# DIAGNOSTIC_ADC.net
KiCad netlist of a schematic drawn in Altium Designer
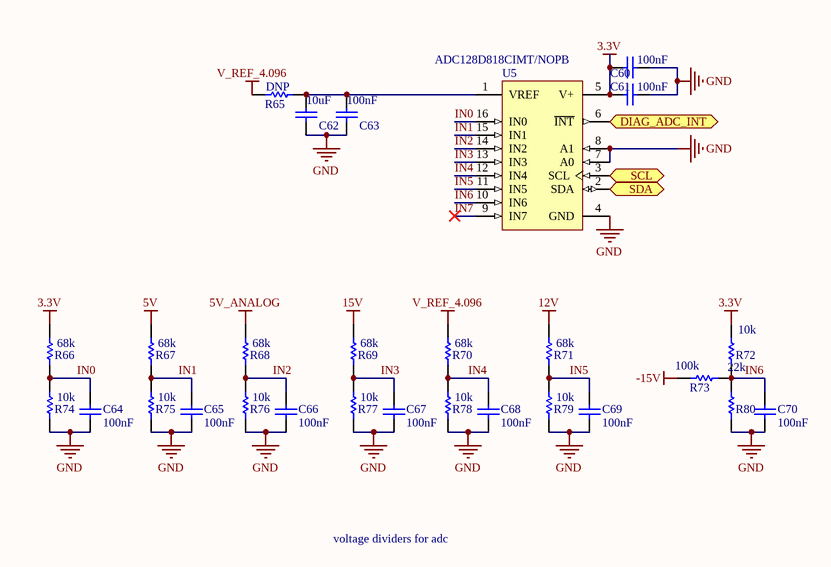
[diagram p0: DIAGNOSTIC_ADC.SchDoc]

(export (version "E")
  (design (tool "Eeschema 10.0.6"))
  (components
    (comp (ref "C60")
      (value "100nF")
      (footprint "CAPC0402(1005)60_L")
      (description "0402 (1005 Metric) Chip Capacitor")
      (fields (field (name "Comment") "CAP0402"))
      (libsource (lib "Altium Content Vault") (part "CMP-1590-00004-1"))
    )
    (comp (ref "C61")
      (value "100nF")
      (footprint "CAPC0402(1005)60_L")
      (description "0402 (1005 Metric) Chip Capacitor")
      (fields (field (name "Comment") "CAP0402"))
      (libsource (lib "Altium Content Vault") (part "CMP-1590-00004-1"))
    )
    (comp (ref "C62")
      (value "10uF")
      (footprint "CAPC0805(2012)145_L")
      (description "0805 (2012 Metric) Chip Capacitor")
      (fields (field (name "Comment") "CAP0805"))
      (libsource (lib "Altium Content Vault") (part "CMP-1590-00003-1"))
    )
    (comp (ref "C63")
      (value "100nF")
      (footprint "CAPC0402(1005)60_L")
      (description "0402 (1005 Metric) Chip Capacitor")
      (fields (field (name "Comment") "CAP0402"))
      (libsource (lib "Altium Content Vault") (part "CMP-1590-00004-1"))
    )
    (comp (ref "C64")
      (value "100nF")
      (footprint "CAPC0402(1005)60_L")
      (description "0402 (1005 Metric) Chip Capacitor")
      (fields (field (name "Comment") "CAP0402"))
      (libsource (lib "Altium Content Vault") (part "CMP-1590-00004-1"))
    )
    (comp (ref "C65")
      (value "100nF")
      (footprint "CAPC0402(1005)60_L")
      (description "0402 (1005 Metric) Chip Capacitor")
      (fields (field (name "Comment") "CAP0402"))
      (libsource (lib "Altium Content Vault") (part "CMP-1590-00004-1"))
    )
    (comp (ref "C66")
      (value "100nF")
      (footprint "CAPC0402(1005)60_L")
      (description "0402 (1005 Metric) Chip Capacitor")
      (fields (field (name "Comment") "CAP0402"))
      (libsource (lib "Altium Content Vault") (part "CMP-1590-00004-1"))
    )
    (comp (ref "C67")
      (value "100nF")
      (footprint "CAPC0402(1005)60_L")
      (description "0402 (1005 Metric) Chip Capacitor")
      (fields (field (name "Comment") "CAP0402"))
      (libsource (lib "Altium Content Vault") (part "CMP-1590-00004-1"))
    )
    (comp (ref "C68")
      (value "100nF")
      (footprint "CAPC0402(1005)60_L")
      (description "0402 (1005 Metric) Chip Capacitor")
      (fields (field (name "Comment") "CAP0402"))
      (libsource (lib "Altium Content Vault") (part "CMP-1590-00004-1"))
    )
    (comp (ref "C69")
      (value "100nF")
      (footprint "CAPC0402(1005)60_L")
      (description "0402 (1005 Metric) Chip Capacitor")
      (fields (field (name "Comment") "CAP0402"))
      (libsource (lib "Altium Content Vault") (part "CMP-1590-00004-1"))
    )
    (comp (ref "C70")
      (value "100nF")
      (footprint "CAPC0402(1005)60_L")
      (description "0402 (1005 Metric) Chip Capacitor")
      (fields (field (name "Comment") "CAP0402"))
      (libsource (lib "Altium Content Vault") (part "CMP-1590-00004-1"))
    )
    (comp (ref "R65")
      (value "DNP")
      (footprint "RESC0402(1005)_L")
      (description "0402 (1005 Metric) Chip Resistor")
      (fields (field (name "Comment") "RES0402"))
      (libsource (lib "Altium Content Vault") (part "CMP-1591-00004-1"))
    )
    (comp (ref "R66")
      (value "68k")
      (footprint "RESC0402(1005)_L")
      (description "0402 (1005 Metric) Chip Resistor")
      (fields (field (name "Comment") "RES0402"))
      (libsource (lib "Altium Content Vault") (part "CMP-1591-00004-1"))
    )
    (comp (ref "R67")
      (value "68k")
      (footprint "RESC0402(1005)_L")
      (description "0402 (1005 Metric) Chip Resistor")
      (fields (field (name "Comment") "RES0402"))
      (libsource (lib "Altium Content Vault") (part "CMP-1591-00004-1"))
    )
    (comp (ref "R68")
      (value "68k")
      (footprint "RESC0402(1005)_L")
      (description "0402 (1005 Metric) Chip Resistor")
      (fields (field (name "Comment") "RES0402"))
      (libsource (lib "Altium Content Vault") (part "CMP-1591-00004-1"))
    )
    (comp (ref "R69")
      (value "68k")
      (footprint "RESC0402(1005)_L")
      (description "0402 (1005 Metric) Chip Resistor")
      (fields (field (name "Comment") "RES0402"))
      (libsource (lib "Altium Content Vault") (part "CMP-1591-00004-1"))
    )
    (comp (ref "R70")
      (value "68k")
      (footprint "RESC0402(1005)_L")
      (description "0402 (1005 Metric) Chip Resistor")
      (fields (field (name "Comment") "RES0402"))
      (libsource (lib "Altium Content Vault") (part "CMP-1591-00004-1"))
    )
    (comp (ref "R71")
      (value "68k")
      (footprint "RESC0402(1005)_L")
      (description "0402 (1005 Metric) Chip Resistor")
      (fields (field (name "Comment") "RES0402"))
      (libsource (lib "Altium Content Vault") (part "CMP-1591-00004-1"))
    )
    (comp (ref "R72")
      (value "10k")
      (footprint "RESC0402(1005)_L")
      (description "0402 (1005 Metric) Chip Resistor")
      (fields (field (name "Comment") "RES0402"))
      (libsource (lib "Altium Content Vault") (part "CMP-1591-00004-1"))
    )
    (comp (ref "R73")
      (value "100k")
      (footprint "RESC0402(1005)_L")
      (description "0402 (1005 Metric) Chip Resistor")
      (fields (field (name "Comment") "RES0402"))
      (libsource (lib "Altium Content Vault") (part "CMP-1591-00004-1"))
    )
    (comp (ref "R74")
      (value "10k")
      (footprint "RESC0402(1005)_L")
      (description "0402 (1005 Metric) Chip Resistor")
      (fields (field (name "Comment") "RES0402"))
      (libsource (lib "Altium Content Vault") (part "CMP-1591-00004-1"))
    )
    (comp (ref "R75")
      (value "10k")
      (footprint "RESC0402(1005)_L")
      (description "0402 (1005 Metric) Chip Resistor")
      (fields (field (name "Comment") "RES0402"))
      (libsource (lib "Altium Content Vault") (part "CMP-1591-00004-1"))
    )
    (comp (ref "R76")
      (value "10k")
      (footprint "RESC0402(1005)_L")
      (description "0402 (1005 Metric) Chip Resistor")
      (fields (field (name "Comment") "RES0402"))
      (libsource (lib "Altium Content Vault") (part "CMP-1591-00004-1"))
    )
    (comp (ref "R77")
      (value "10k")
      (footprint "RESC0402(1005)_L")
      (description "0402 (1005 Metric) Chip Resistor")
      (fields (field (name "Comment") "RES0402"))
      (libsource (lib "Altium Content Vault") (part "CMP-1591-00004-1"))
    )
    (comp (ref "R78")
      (value "10k")
      (footprint "RESC0402(1005)_L")
      (description "0402 (1005 Metric) Chip Resistor")
      (fields (field (name "Comment") "RES0402"))
      (libsource (lib "Altium Content Vault") (part "CMP-1591-00004-1"))
    )
    (comp (ref "R79")
      (value "10k")
      (footprint "RESC0402(1005)_L")
      (description "0402 (1005 Metric) Chip Resistor")
      (fields (field (name "Comment") "RES0402"))
      (libsource (lib "Altium Content Vault") (part "CMP-1591-00004-1"))
    )
    (comp (ref "R80")
      (value "22k")
      (footprint "RESC0402(1005)_L")
      (description "0402 (1005 Metric) Chip Resistor")
      (fields (field (name "Comment") "RES0402"))
      (libsource (lib "Altium Content Vault") (part "CMP-1591-00004-1"))
    )
    (comp (ref "U5")
      (value "ADC128D818CIMT/NOPB")
      (footprint "MTC16_N")
      (fields (field (name "MANUFACTURER") "National Semiconductor"))
      (libsource (lib "Altium Content Vault") (part "CON-ADC-ADC128D818-16"))
    )
  )
  (nets
    (net (code "1") (name "-15V") (class "Default")
      (node (ref "R73") (pin "1") (pinfunction "1_1") (pintype "passive"))
    )
    (net (code "2") (name "/DIAG_ADC_INT") (class "Default")
      (node (ref "U5") (pin "6") (pinfunction "~{INT}_6") (pintype "output"))
    )
    (net (code "3") (name "/IN0") (class "Default")
      (node (ref "C64") (pin "2") (pinfunction "2_2") (pintype "passive"))
      (node (ref "R66") (pin "2") (pinfunction "2_2") (pintype "passive"))
      (node (ref "R74") (pin "1") (pinfunction "1_1") (pintype "passive"))
      (node (ref "U5") (pin "16") (pinfunction "IN0_16") (pintype "input"))
    )
    (net (code "4") (name "/IN1") (class "Default")
      (node (ref "C65") (pin "2") (pinfunction "2_2") (pintype "passive"))
      (node (ref "R67") (pin "2") (pinfunction "2_2") (pintype "passive"))
      (node (ref "R75") (pin "1") (pinfunction "1_1") (pintype "passive"))
      (node (ref "U5") (pin "15") (pinfunction "IN1_15") (pintype "input"))
    )
    (net (code "5") (name "/IN2") (class "Default")
      (node (ref "C66") (pin "2") (pinfunction "2_2") (pintype "passive"))
      (node (ref "R68") (pin "2") (pinfunction "2_2") (pintype "passive"))
      (node (ref "R76") (pin "1") (pinfunction "1_1") (pintype "passive"))
      (node (ref "U5") (pin "14") (pinfunction "IN2_14") (pintype "input"))
    )
    (net (code "6") (name "/IN3") (class "Default")
      (node (ref "C67") (pin "2") (pinfunction "2_2") (pintype "passive"))
      (node (ref "R69") (pin "2") (pinfunction "2_2") (pintype "passive"))
      (node (ref "R77") (pin "1") (pinfunction "1_1") (pintype "passive"))
      (node (ref "U5") (pin "13") (pinfunction "IN3_13") (pintype "input"))
    )
    (net (code "7") (name "/IN4") (class "Default")
      (node (ref "C68") (pin "2") (pinfunction "2_2") (pintype "passive"))
      (node (ref "R70") (pin "2") (pinfunction "2_2") (pintype "passive"))
      (node (ref "R78") (pin "1") (pinfunction "1_1") (pintype "passive"))
      (node (ref "U5") (pin "12") (pinfunction "IN4_12") (pintype "input"))
    )
    (net (code "8") (name "/IN5") (class "Default")
      (node (ref "C69") (pin "2") (pinfunction "2_2") (pintype "passive"))
      (node (ref "R71") (pin "2") (pinfunction "2_2") (pintype "passive"))
      (node (ref "R79") (pin "1") (pinfunction "1_1") (pintype "passive"))
      (node (ref "U5") (pin "11") (pinfunction "IN5_11") (pintype "input"))
    )
    (net (code "9") (name "/IN6") (class "Default")
      (node (ref "C70") (pin "2") (pinfunction "2_2") (pintype "passive"))
      (node (ref "R72") (pin "2") (pinfunction "2_2") (pintype "passive"))
      (node (ref "R73") (pin "2") (pinfunction "2_2") (pintype "passive"))
      (node (ref "R80") (pin "1") (pinfunction "1_1") (pintype "passive"))
      (node (ref "U5") (pin "10") (pinfunction "IN6_10") (pintype "input"))
    )
    (net (code "10") (name "/IN7") (class "Default")
      (node (ref "U5") (pin "9") (pinfunction "IN7_9") (pintype "input+no_connect"))
    )
    (net (code "11") (name "/SCL") (class "Default")
      (node (ref "U5") (pin "3") (pinfunction "SCL_3") (pintype "input"))
    )
    (net (code "12") (name "/SDA") (class "Default")
      (node (ref "U5") (pin "2") (pinfunction "SDA_2") (pintype "bidirectional"))
    )
    (net (code "13") (name "3.3V") (class "Default")
      (node (ref "C60") (pin "1") (pinfunction "1_1") (pintype "passive"))
      (node (ref "C61") (pin "1") (pinfunction "1_1") (pintype "passive"))
      (node (ref "R66") (pin "1") (pinfunction "1_1") (pintype "passive"))
      (node (ref "R72") (pin "1") (pinfunction "1_1") (pintype "passive"))
      (node (ref "U5") (pin "5") (pinfunction "V+_5") (pintype "power_in"))
    )
    (net (code "14") (name "5V") (class "Default")
      (node (ref "R67") (pin "1") (pinfunction "1_1") (pintype "passive"))
    )
    (net (code "15") (name "5V_ANALOG") (class "Default")
      (node (ref "R68") (pin "1") (pinfunction "1_1") (pintype "passive"))
    )
    (net (code "16") (name "12V") (class "Default")
      (node (ref "R71") (pin "1") (pinfunction "1_1") (pintype "passive"))
    )
    (net (code "17") (name "15V") (class "Default")
      (node (ref "R69") (pin "1") (pinfunction "1_1") (pintype "passive"))
    )
    (net (code "18") (name "GND") (class "Default")
      (node (ref "C60") (pin "2") (pinfunction "2_2") (pintype "passive"))
      (node (ref "C61") (pin "2") (pinfunction "2_2") (pintype "passive"))
      (node (ref "C62") (pin "1") (pinfunction "1_1") (pintype "passive"))
      (node (ref "C63") (pin "2") (pinfunction "2_2") (pintype "passive"))
      (node (ref "C64") (pin "1") (pinfunction "1_1") (pintype "passive"))
      (node (ref "C65") (pin "1") (pinfunction "1_1") (pintype "passive"))
      (node (ref "C66") (pin "1") (pinfunction "1_1") (pintype "passive"))
      (node (ref "C67") (pin "1") (pinfunction "1_1") (pintype "passive"))
      (node (ref "C68") (pin "1") (pinfunction "1_1") (pintype "passive"))
      (node (ref "C69") (pin "1") (pinfunction "1_1") (pintype "passive"))
      (node (ref "C70") (pin "1") (pinfunction "1_1") (pintype "passive"))
      (node (ref "R74") (pin "2") (pinfunction "2_2") (pintype "passive"))
      (node (ref "R75") (pin "2") (pinfunction "2_2") (pintype "passive"))
      (node (ref "R76") (pin "2") (pinfunction "2_2") (pintype "passive"))
      (node (ref "R77") (pin "2") (pinfunction "2_2") (pintype "passive"))
      (node (ref "R78") (pin "2") (pinfunction "2_2") (pintype "passive"))
      (node (ref "R79") (pin "2") (pinfunction "2_2") (pintype "passive"))
      (node (ref "R80") (pin "2") (pinfunction "2_2") (pintype "passive"))
      (node (ref "U5") (pin "4") (pinfunction "GND_4") (pintype "power_in"))
      (node (ref "U5") (pin "7") (pinfunction "A0_7") (pintype "input"))
      (node (ref "U5") (pin "8") (pinfunction "A1_8") (pintype "input"))
    )
    (net (code "19") (name "Net-(U5-VREF)") (class "Default")
      (node (ref "C62") (pin "2") (pinfunction "2_2") (pintype "passive"))
      (node (ref "C63") (pin "1") (pinfunction "1_1") (pintype "passive"))
      (node (ref "R65") (pin "1") (pinfunction "1_1") (pintype "passive"))
      (node (ref "U5") (pin "1") (pinfunction "VREF_1") (pintype "power_in"))
    )
    (net (code "20") (name "V_REF_4.096") (class "Default")
      (node (ref "R65") (pin "2") (pinfunction "2_2") (pintype "passive"))
      (node (ref "R70") (pin "1") (pinfunction "1_1") (pintype "passive"))
    )
  )
)
